# SCH_555-Circuit_2025-03-12.net
KiCad netlist of a schematic drawn in EasyEDA
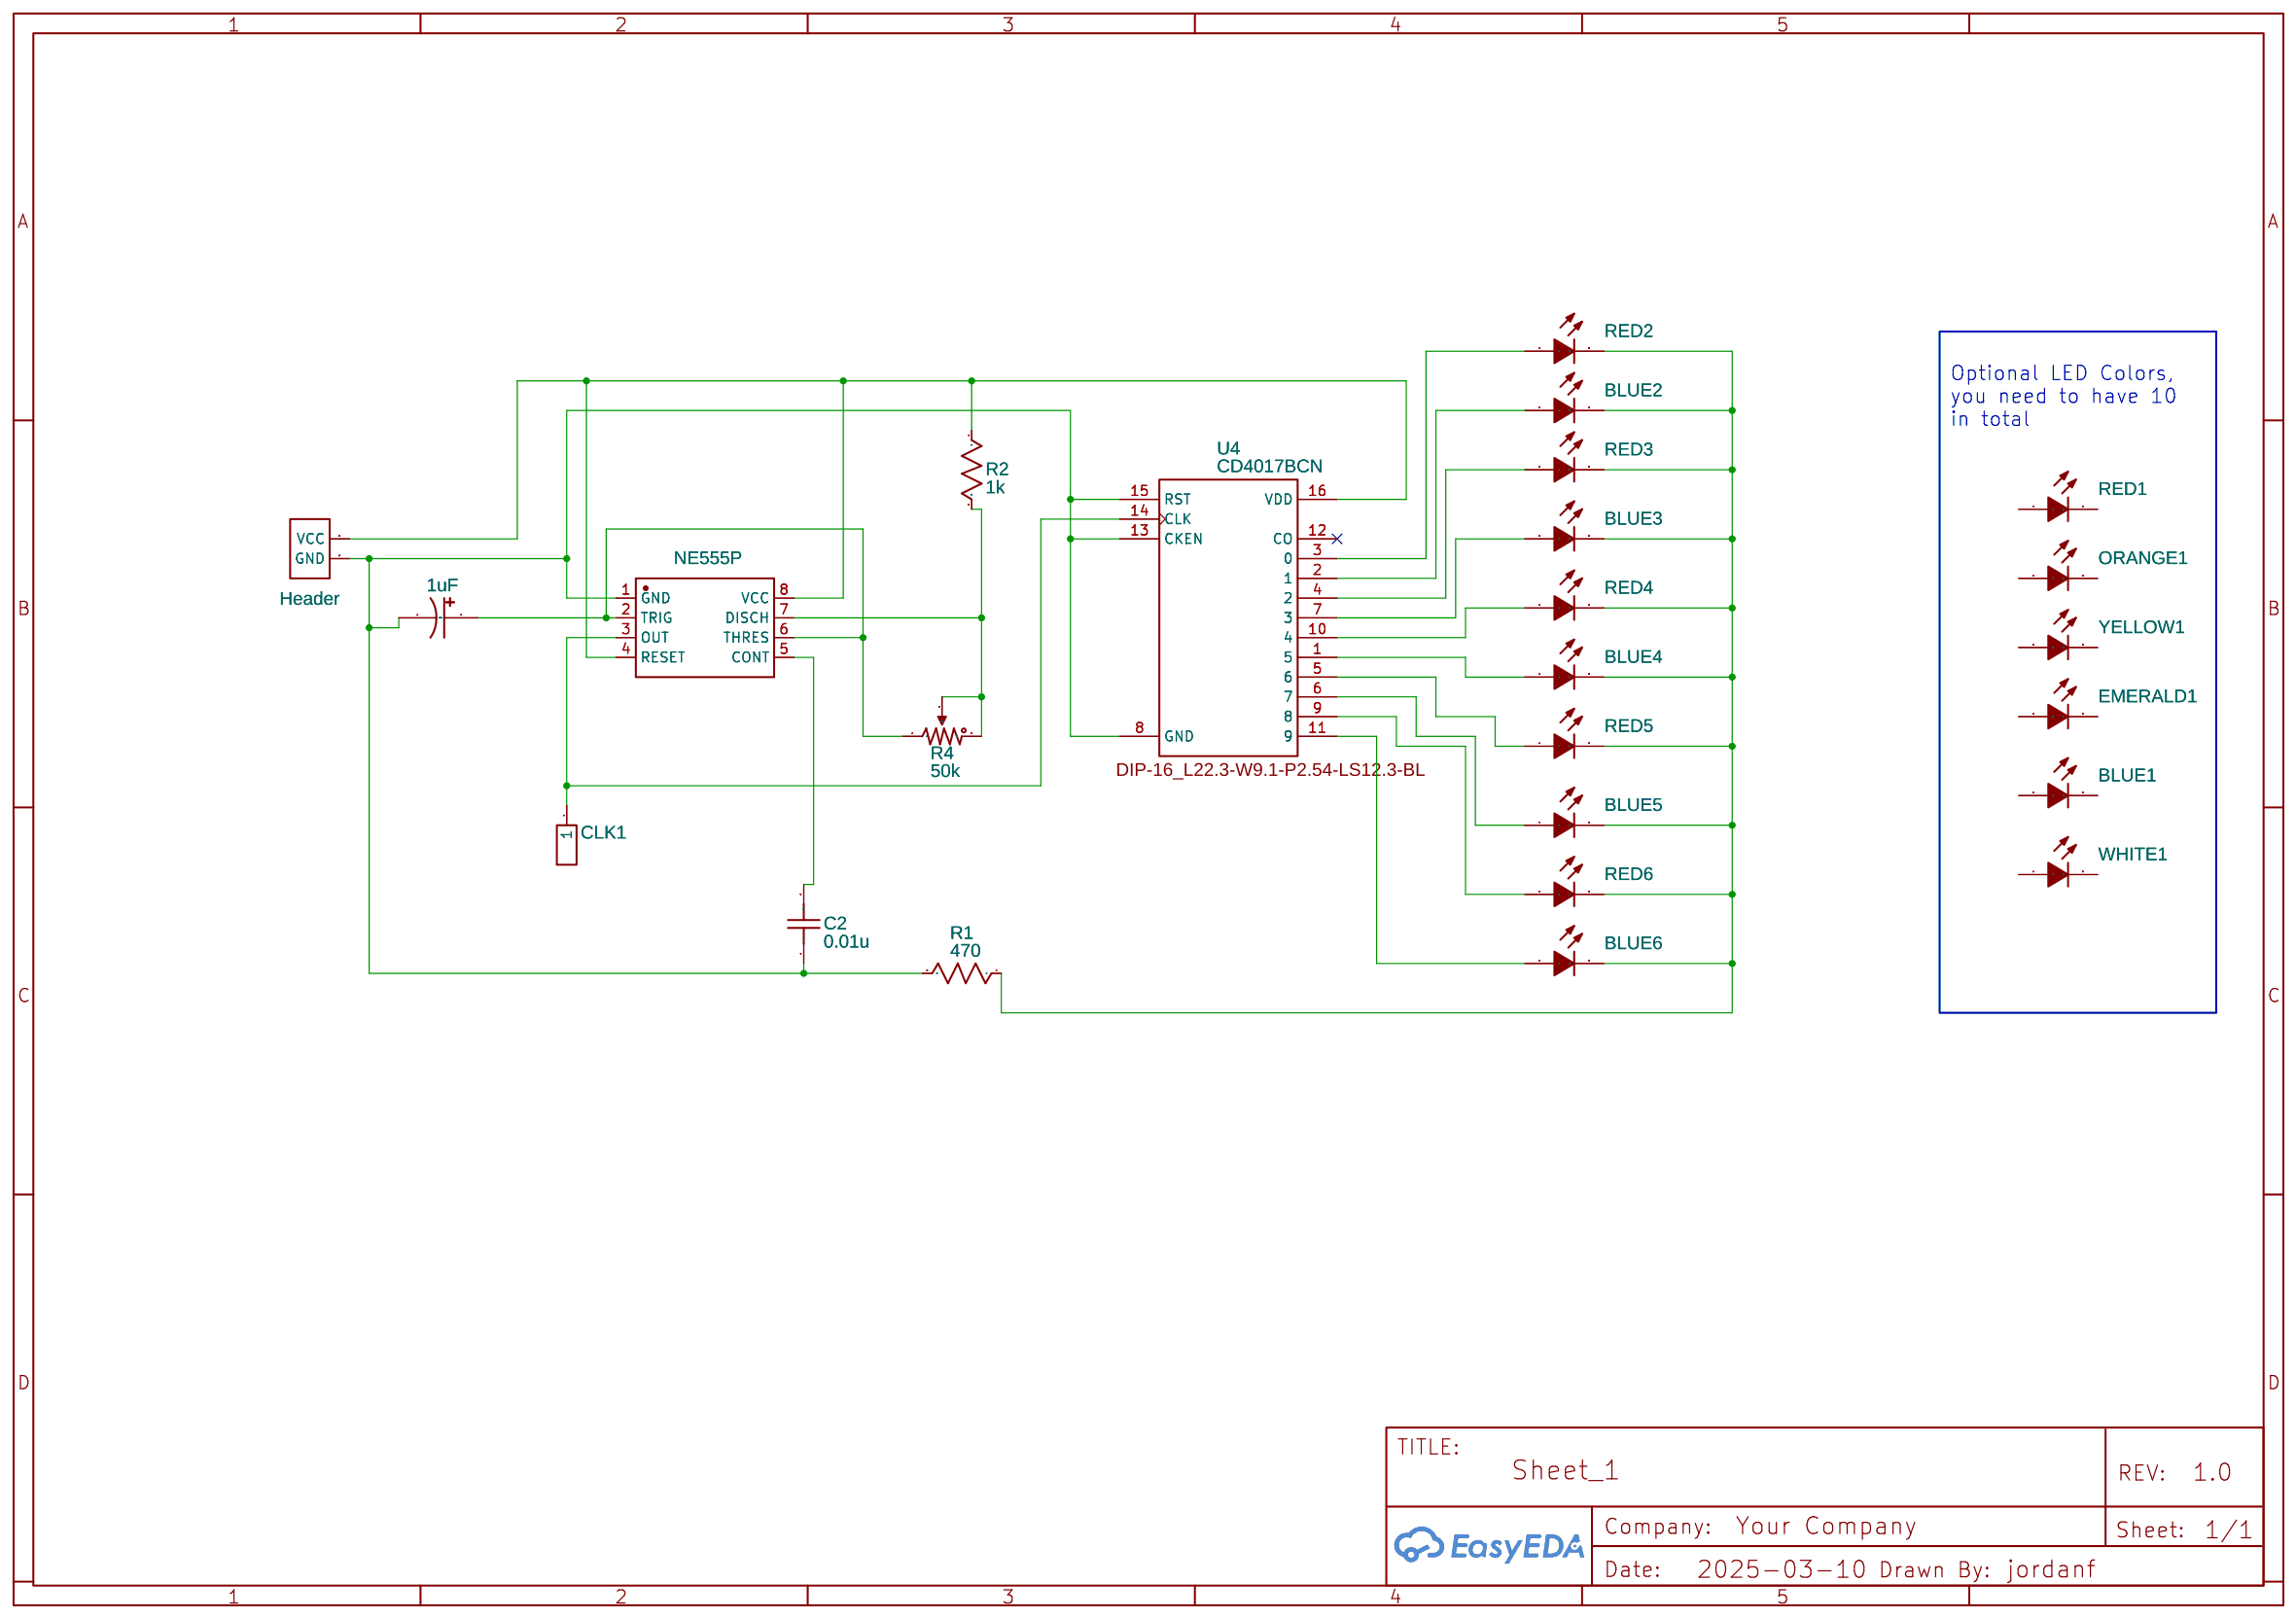
[diagram p0: schematic sheet]

(export (version "E")
  (design (tool "Eeschema 10.0.6"))
  (components
    (comp (ref "BLUE1") (value "LED_5MM") (libsource (lib "") (part "LED_5MM_1")))
    (comp (ref "BLUE2") (value "LED_5MM") (libsource (lib "") (part "LED_5MM_1")))
    (comp (ref "BLUE3") (value "LED_5MM") (libsource (lib "") (part "LED_5MM_1")))
    (comp (ref "BLUE4") (value "LED_5MM") (libsource (lib "") (part "LED_5MM_1")))
    (comp (ref "BLUE5") (value "LED_5MM") (libsource (lib "") (part "LED_5MM_1")))
    (comp (ref "BLUE6") (value "LED_5MM") (libsource (lib "") (part "LED_5MM_1")))
    (comp (ref "C1")
      (value "1uF")
      (fields (field (name "Manufacturer Part") "UVZ1H010MDD") (field (name "Manufacturer") "Nichicon(尼吉康)"))
      (libsource (lib "") (part "UVZ1H010MDD"))
    )
    (comp (ref "C2") (value "0.01u") (libsource (lib "") (part "C_0603_US")))
    (comp (ref "CLK1")
      (value "C81276")
      (fields
        (field (name "Manufacturer Part") "2.54-1*1P针")
        (field (name "Manufacturer") "BOOMELE(Boom Precision Elec)")
      )
      (libsource (lib "") (part "Header-Male-2.54_1x1"))
    )
    (comp (ref "EMERALD1") (value "LED_5MM") (libsource (lib "") (part "LED_5MM_4")))
    (comp (ref "H1") (value "Header") (libsource (lib "") (part "HEADER-FEMALE-2.54_1X2")))
    (comp (ref "ORANGE1") (value "LED_5MM") (libsource (lib "") (part "LED_5MM")))
    (comp (ref "R1")
      (value "470")
      (fields (field (name "Manufacturer Part") "?"))
      (libsource (lib "") (part "Resistor"))
    )
    (comp (ref "R2")
      (value "1k")
      (fields (field (name "Manufacturer Part") "?"))
      (libsource (lib "") (part "Resistor_1"))
    )
    (comp (ref "R4")
      (value "50k")
      (fields (field (name "Manufacturer Part") "?"))
      (libsource (lib "") (part "Potentiometer"))
    )
    (comp (ref "RED1") (value "LED_5MM") (libsource (lib "") (part "LED_5MM_2")))
    (comp (ref "RED2") (value "LED_5MM") (libsource (lib "") (part "LED_5MM_2")))
    (comp (ref "RED3") (value "LED_5MM") (libsource (lib "") (part "LED_5MM_2")))
    (comp (ref "RED4") (value "LED_5MM") (libsource (lib "") (part "LED_5MM_2")))
    (comp (ref "RED5") (value "LED_5MM") (libsource (lib "") (part "LED_5MM_2")))
    (comp (ref "RED6") (value "LED_5MM") (libsource (lib "") (part "LED_5MM_2")))
    (comp (ref "U2")
      (value "NE555P")
      (fields (field (name "Manufacturer") "TI(德州仪器)"))
      (libsource (lib "") (part "NE555P"))
    )
    (comp (ref "U4") (value "CD4017BCN") (libsource (lib "") (part "CD4017BCN")))
    (comp (ref "WHITE1") (value "LED_5MM") (libsource (lib "") (part "LED_5MM_5")))
    (comp (ref "YELLOW1") (value "LED_5MM") (libsource (lib "") (part "LED_5MM_3")))
  )
  (nets
    (net (code "1") (name "Net-(BLUE2-A)") (class "Default")
      (node (ref "BLUE2") (pin "1") (pinfunction "A_1") (pintype "input"))
      (node (ref "U4") (pin "2") (pinfunction "1_2") (pintype "output"))
    )
    (net (code "2") (name "Net-(BLUE2-K)") (class "Default")
      (node (ref "BLUE2") (pin "2") (pinfunction "K_2") (pintype "input"))
      (node (ref "BLUE3") (pin "2") (pinfunction "K_2") (pintype "input"))
      (node (ref "BLUE4") (pin "2") (pinfunction "K_2") (pintype "input"))
      (node (ref "BLUE5") (pin "2") (pinfunction "K_2") (pintype "input"))
      (node (ref "BLUE6") (pin "2") (pinfunction "K_2") (pintype "input"))
      (node (ref "R1") (pin "1") (pinfunction "1_1") (pintype "unspecified"))
      (node (ref "RED2") (pin "2") (pinfunction "K_2") (pintype "input"))
      (node (ref "RED3") (pin "2") (pinfunction "K_2") (pintype "input"))
      (node (ref "RED4") (pin "2") (pinfunction "K_2") (pintype "input"))
      (node (ref "RED5") (pin "2") (pinfunction "K_2") (pintype "input"))
      (node (ref "RED6") (pin "2") (pinfunction "K_2") (pintype "input"))
    )
    (net (code "3") (name "Net-(BLUE3-A)") (class "Default")
      (node (ref "BLUE3") (pin "1") (pinfunction "A_1") (pintype "input"))
      (node (ref "U4") (pin "7") (pinfunction "3_7") (pintype "output"))
    )
    (net (code "4") (name "Net-(BLUE4-A)") (class "Default")
      (node (ref "BLUE4") (pin "1") (pinfunction "A_1") (pintype "input"))
      (node (ref "U4") (pin "1") (pinfunction "5_1") (pintype "output"))
    )
    (net (code "5") (name "Net-(BLUE5-A)") (class "Default")
      (node (ref "BLUE5") (pin "1") (pinfunction "A_1") (pintype "input"))
      (node (ref "U4") (pin "6") (pinfunction "7_6") (pintype "output"))
    )
    (net (code "6") (name "Net-(BLUE6-A)") (class "Default")
      (node (ref "BLUE6") (pin "1") (pinfunction "A_1") (pintype "input"))
      (node (ref "U4") (pin "11") (pinfunction "9_11") (pintype "output"))
    )
    (net (code "7") (name "Net-(H1-GND)") (class "Default")
      (node (ref "C1") (pin "2") (pinfunction "2_2") (pintype "unspecified"))
      (node (ref "C2") (pin "1") (pinfunction "1_1") (pintype "unspecified"))
      (node (ref "H1") (pin "2") (pinfunction "GND_2") (pintype "unspecified"))
      (node (ref "R1") (pin "2") (pinfunction "2_2") (pintype "unspecified"))
      (node (ref "U2") (pin "1") (pinfunction "GND_1") (pintype "unspecified"))
      (node (ref "U4") (pin "13") (pinfunction "CKEN_13") (pintype "unspecified"))
      (node (ref "U4") (pin "15") (pinfunction "RST_15") (pintype "unspecified"))
      (node (ref "U4") (pin "8") (pinfunction "GND_8") (pintype "passive"))
    )
    (net (code "8") (name "Net-(H1-VCC)") (class "Default")
      (node (ref "H1") (pin "1") (pinfunction "VCC_1") (pintype "unspecified"))
      (node (ref "R2") (pin "1") (pinfunction "1_1") (pintype "unspecified"))
      (node (ref "U2") (pin "4") (pinfunction "RESET_4") (pintype "unspecified"))
      (node (ref "U2") (pin "8") (pinfunction "VCC_8") (pintype "unspecified"))
      (node (ref "U4") (pin "16") (pinfunction "VDD_16") (pintype "passive"))
    )
    (net (code "9") (name "Net-(R4-2)") (class "Default")
      (node (ref "R2") (pin "2") (pinfunction "2_2") (pintype "unspecified"))
      (node (ref "R4") (pin "2") (pinfunction "3_2") (pintype "unspecified"))
      (node (ref "R4") (pin "3") (pinfunction "2_3") (pintype "unspecified"))
      (node (ref "U2") (pin "7") (pinfunction "DISCH_7") (pintype "unspecified"))
    )
    (net (code "10") (name "Net-(RED2-A)") (class "Default")
      (node (ref "RED2") (pin "1") (pinfunction "A_1") (pintype "input"))
      (node (ref "U4") (pin "3") (pinfunction "0_3") (pintype "output"))
    )
    (net (code "11") (name "Net-(RED3-A)") (class "Default")
      (node (ref "RED3") (pin "1") (pinfunction "A_1") (pintype "input"))
      (node (ref "U4") (pin "4") (pinfunction "2_4") (pintype "output"))
    )
    (net (code "12") (name "Net-(RED4-A)") (class "Default")
      (node (ref "RED4") (pin "1") (pinfunction "A_1") (pintype "input"))
      (node (ref "U4") (pin "10") (pinfunction "4_10") (pintype "output"))
    )
    (net (code "13") (name "Net-(RED5-A)") (class "Default")
      (node (ref "RED5") (pin "1") (pinfunction "A_1") (pintype "input"))
      (node (ref "U4") (pin "5") (pinfunction "6_5") (pintype "output"))
    )
    (net (code "14") (name "Net-(RED6-A)") (class "Default")
      (node (ref "RED6") (pin "1") (pinfunction "A_1") (pintype "input"))
      (node (ref "U4") (pin "9") (pinfunction "8_9") (pintype "output"))
    )
    (net (code "15") (name "Net-(U2-CONT)") (class "Default")
      (node (ref "C2") (pin "2") (pinfunction "2_2") (pintype "unspecified"))
      (node (ref "U2") (pin "5") (pinfunction "CONT_5") (pintype "unspecified"))
    )
    (net (code "16") (name "Net-(U2-OUT)") (class "Default")
      (node (ref "CLK1") (pin "1") (pinfunction "1_1") (pintype "unspecified"))
      (node (ref "U2") (pin "3") (pinfunction "OUT_3") (pintype "unspecified"))
      (node (ref "U4") (pin "14") (pinfunction "CLK_14") (pintype "unspecified"))
    )
    (net (code "17") (name "Net-(U2-THRES)") (class "Default")
      (node (ref "C1") (pin "1") (pinfunction "1_1") (pintype "unspecified"))
      (node (ref "R4") (pin "1") (pinfunction "1_1") (pintype "unspecified"))
      (node (ref "U2") (pin "2") (pinfunction "TRIG_2") (pintype "unspecified"))
      (node (ref "U2") (pin "6") (pinfunction "THRES_6") (pintype "unspecified"))
    )
    (net (code "18") (name "unconnected-(BLUE1-A-Pad1)") (class "Default")
      (node (ref "BLUE1") (pin "1") (pinfunction "A_1") (pintype "input"))
    )
    (net (code "19") (name "unconnected-(BLUE1-K-Pad2)") (class "Default")
      (node (ref "BLUE1") (pin "2") (pinfunction "K_2") (pintype "input"))
    )
    (net (code "20") (name "unconnected-(EMERALD1-A-Pad1)") (class "Default")
      (node (ref "EMERALD1") (pin "1") (pinfunction "A_1") (pintype "input"))
    )
    (net (code "21") (name "unconnected-(EMERALD1-K-Pad2)") (class "Default")
      (node (ref "EMERALD1") (pin "2") (pinfunction "K_2") (pintype "input"))
    )
    (net (code "22") (name "unconnected-(ORANGE1-A-Pad1)") (class "Default")
      (node (ref "ORANGE1") (pin "1") (pinfunction "A_1") (pintype "input"))
    )
    (net (code "23") (name "unconnected-(ORANGE1-K-Pad2)") (class "Default")
      (node (ref "ORANGE1") (pin "2") (pinfunction "K_2") (pintype "input"))
    )
    (net (code "24") (name "unconnected-(RED1-A-Pad1)") (class "Default")
      (node (ref "RED1") (pin "1") (pinfunction "A_1") (pintype "input"))
    )
    (net (code "25") (name "unconnected-(RED1-K-Pad2)") (class "Default")
      (node (ref "RED1") (pin "2") (pinfunction "K_2") (pintype "input"))
    )
    (net (code "26") (name "unconnected-(U4-CO-Pad12)") (class "Default")
      (node (ref "U4") (pin "12") (pinfunction "CO_12") (pintype "output+no_connect"))
    )
    (net (code "27") (name "unconnected-(WHITE1-A-Pad1)") (class "Default")
      (node (ref "WHITE1") (pin "1") (pinfunction "A_1") (pintype "input"))
    )
    (net (code "28") (name "unconnected-(WHITE1-K-Pad2)") (class "Default")
      (node (ref "WHITE1") (pin "2") (pinfunction "K_2") (pintype "input"))
    )
    (net (code "29") (name "unconnected-(YELLOW1-A-Pad1)") (class "Default")
      (node (ref "YELLOW1") (pin "1") (pinfunction "A_1") (pintype "input"))
    )
    (net (code "30") (name "unconnected-(YELLOW1-K-Pad2)") (class "Default")
      (node (ref "YELLOW1") (pin "2") (pinfunction "K_2") (pintype "input"))
    )
  )
)
